# SchaltmichAus.net
KiCad netlist of a schematic drawn in Altium Designer
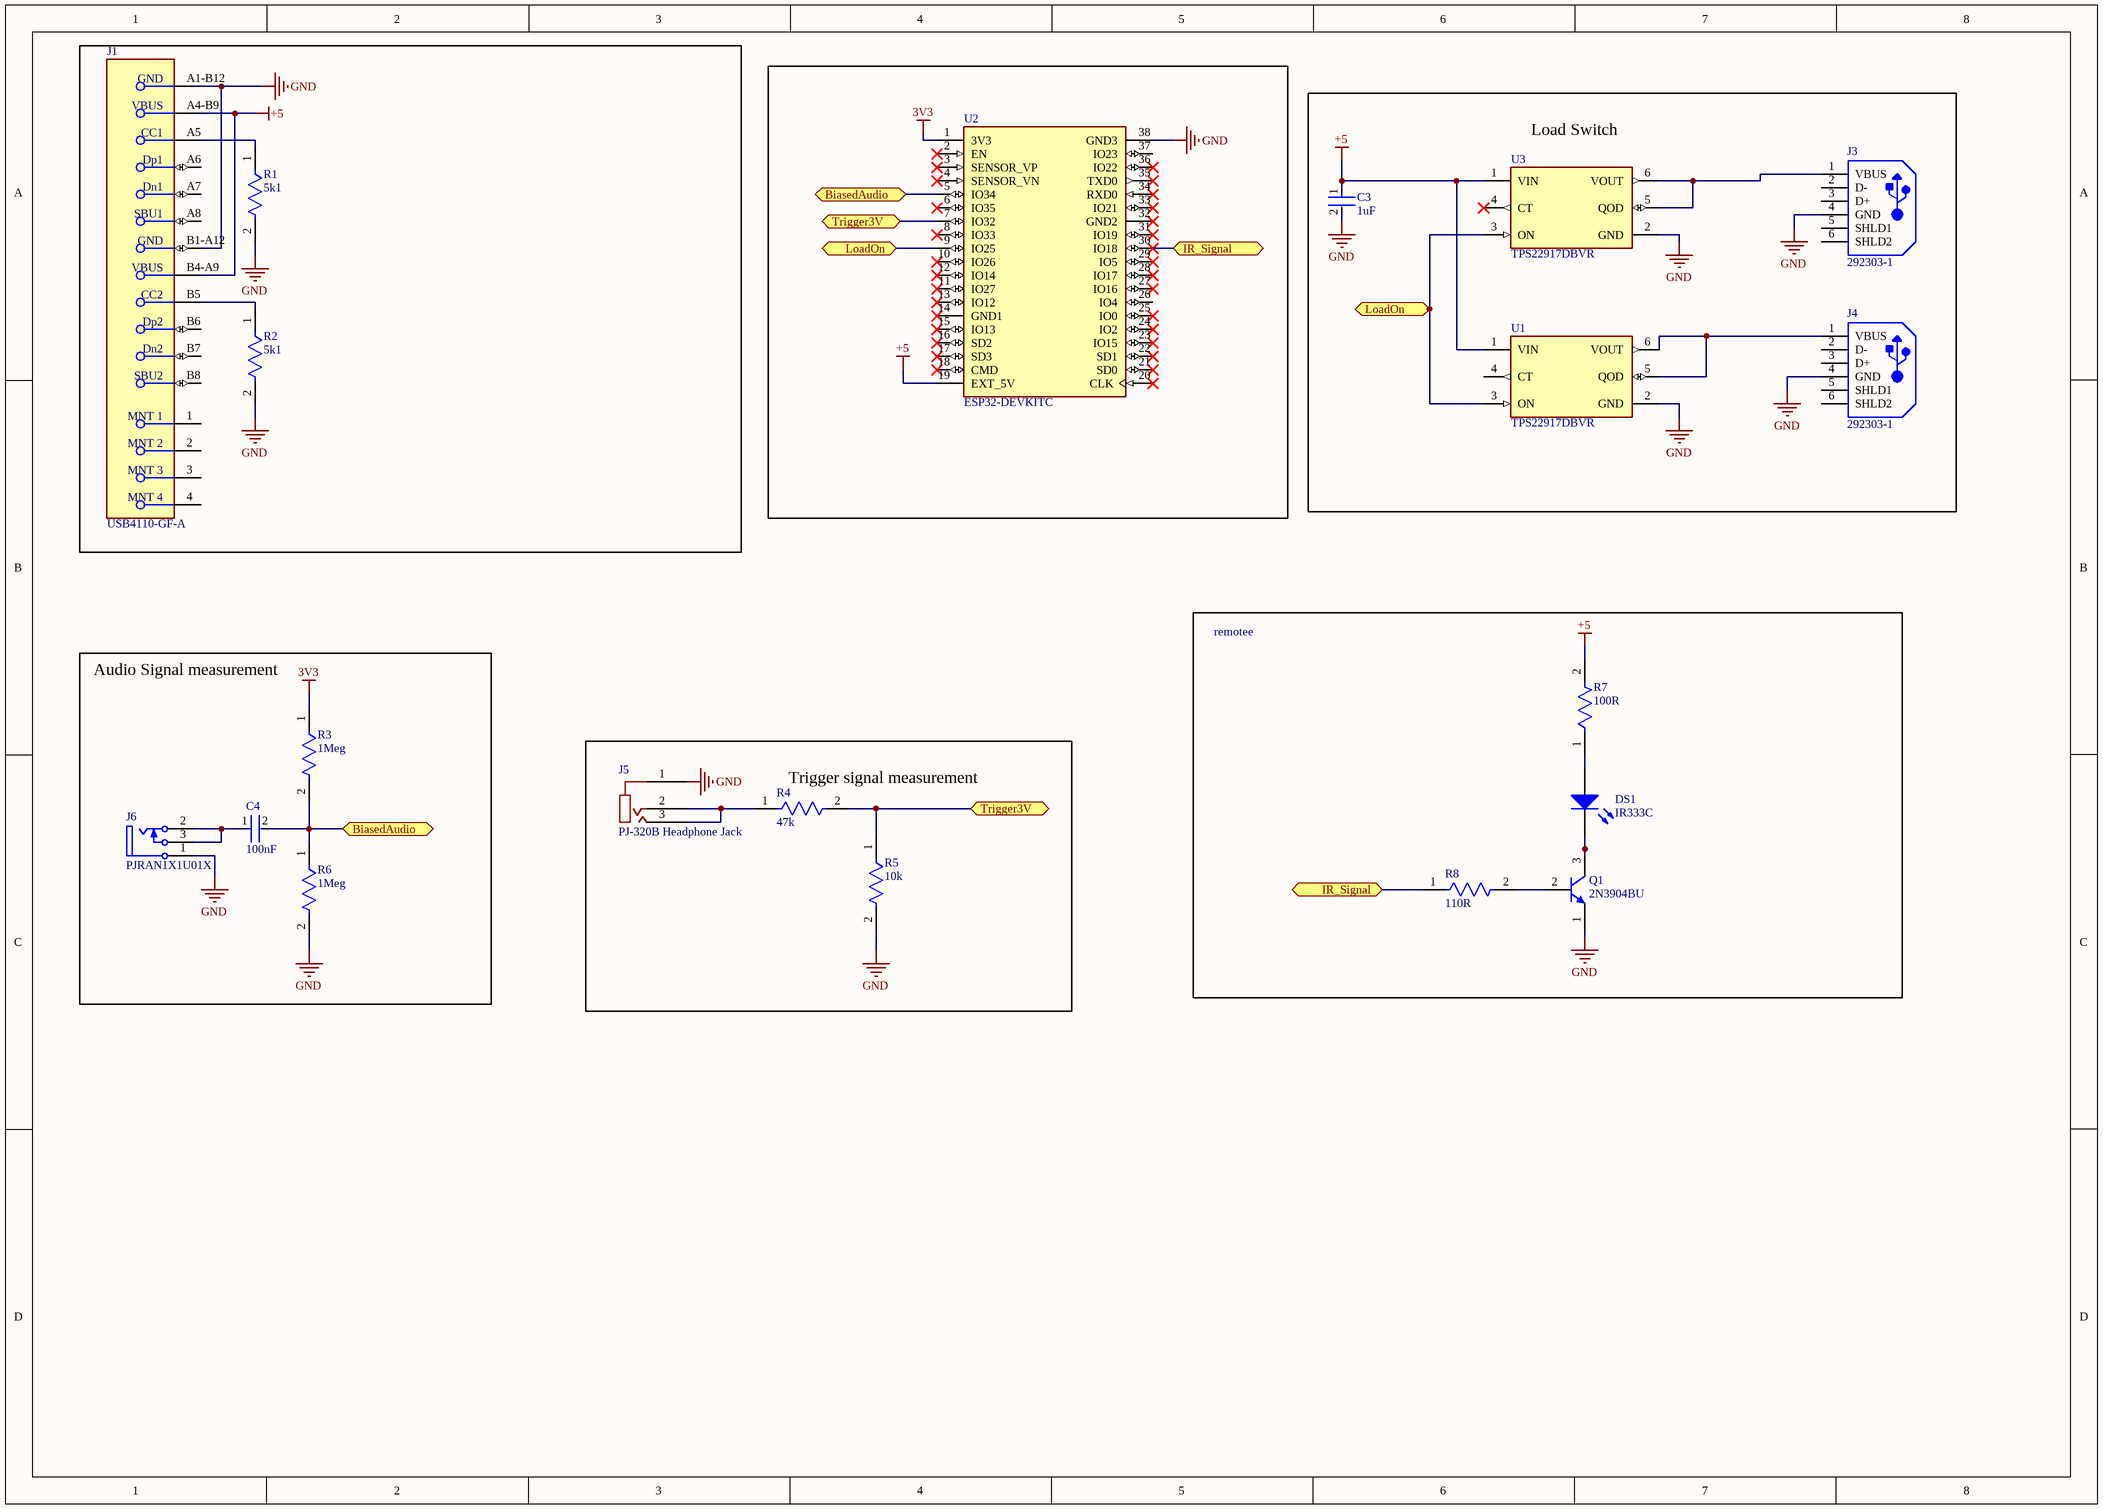
[diagram p0: SchaltmichAus.SchDoc]

(export (version "E")
  (design (tool "Eeschema 10.0.6"))
  (components
    (comp (ref "C3")
      (value "1uF")
      (footprint "FP-CC1206-FD-MFG")
      (description "CAP CER 10UF 50V X5R 1206")
      (fields (field (name "TOLERANCE") "10%"))
      (libsource (lib "Altium Content Vault") (part "b4654b650e69147ec39a6b967a45e02"))
    )
    (comp (ref "C4")
      (value "100nF")
      (footprint "FP-CC1206-FD-MFG")
      (description "CAP CER 10UF 50V X5R 1206")
      (fields (field (name "TOLERANCE") "10%"))
      (libsource (lib "Altium Content Vault") (part "b4654b650e69147ec39a6b967a45e02"))
    )
    (comp (ref "DS1")
      (value "IR333C")
      (footprint "EVRL-IR333C")
      (description "Infrared LED, 1.2 V, -40 to 85 degC, 2-Pin Radial, RoHS, Bulk")
      (fields (field (name "MANUFACTURER") "Everlight Electronics"))
      (libsource (lib "Altium Content Vault") (part "LED-AK-2"))
    )
    (comp (ref "J1")
      (value "USB4110-GF-A")
      (footprint "FP-USB4110-GF-A-MFG")
      (description "CONN USB 2.0 TYPE-C R/A SMT")
      (fields
        (field (name "OCTOPART") "https://octopart.com/usb4110-gf-a-gct-103941985")
        (field (name "MANUFACTURER") "GCT")
      )
      (libsource (lib "Altium Content Vault") (part "e23f2b38bb3c3f98e683ebab9ede730"))
    )
    (comp (ref "J3")
      (value "292303-1")
      (footprint "TE-292303-1_V")
      (fields (field (name "MANUFACTURER") "TE Connectivity"))
      (libsource (lib "Altium Content Vault") (part "USB-4-2SHLD"))
    )
    (comp (ref "J4")
      (value "292303-1")
      (footprint "TE-292303-1_V")
      (fields (field (name "MANUFACTURER") "TE Connectivity"))
      (libsource (lib "Altium Content Vault") (part "USB-4-2SHLD"))
    )
    (comp (ref "J5")
      (value "PJ-320B Headphone Jack")
      (footprint "New footprint 1")
      (description "200mA 3.5mm Headphone Jack 30V SMD Audio Connectors ROHS")
      (libsource (lib "Niko Leimegger") (part "PJ-320BSurface Mount Headphone Jack"))
    )
    (comp (ref "J6")
      (value "PJRAN1X1U01X")
      (footprint "SWIT-PJRAN1X1U01X_V")
      (description "Female Phono Jack, 3 Position, Height 13 mm, Tail Length 4 mm, RoHS, Bulk")
      (fields (field (name "TOLERANCE") "10%"))
      (libsource (lib "Altium Content Vault") (part "JACK-2CD3-TN"))
    )
    (comp (ref "Q1")
      (value "2N3904BU")
      (footprint "FAIR-TO-92")
      (description "NPN General-Purpose Amplifier, 40 V VCEO, 0.2 A, -55 to 150 degC, 2-Pin TO-92, RoHS, Bulk")
      (fields (field (name "MANUFACTURER") "FairchildSemiconductor"))
      (libsource (lib "Altium Content Vault") (part "NPN-E1B2C3-3"))
    )
    (comp (ref "R1")
      (value "5k1")
      (footprint "FP-CRGP1206-IPC_C")
      (description "CRGP1206 100KΩ 0.5W ±100ppm/°C 1% 200V")
      (fields (field (name "MANUFACTURER") "TE") (field (name "TOLERANCE") "0.01"))
      (libsource (lib "Altium Content Vault") (part "1029c3af85768c4190bb7ad29bc67b5"))
    )
    (comp (ref "R2")
      (value "5k1")
      (footprint "FP-CRGP1206-IPC_C")
      (description "CRGP1206 100KΩ 0.5W ±100ppm/°C 1% 200V")
      (fields (field (name "MANUFACTURER") "TE") (field (name "TOLERANCE") "0.01"))
      (libsource (lib "Altium Content Vault") (part "1029c3af85768c4190bb7ad29bc67b5"))
    )
    (comp (ref "R3")
      (value "1Meg")
      (footprint "FP-CRGP1206-IPC_C")
      (description "CRGP1206 100KΩ 0.5W ±100ppm/°C 1% 200V")
      (fields (field (name "MANUFACTURER") "TE") (field (name "TOLERANCE") "0.01"))
      (libsource (lib "Altium Content Vault") (part "1029c3af85768c4190bb7ad29bc67b5"))
    )
    (comp (ref "R4")
      (value "47k")
      (footprint "FP-CRGP1206-IPC_C")
      (description "CRGP1206 100KΩ 0.5W ±100ppm/°C 1% 200V")
      (fields (field (name "MANUFACTURER") "TE") (field (name "TOLERANCE") "0.01"))
      (libsource (lib "Altium Content Vault") (part "1029c3af85768c4190bb7ad29bc67b5"))
    )
    (comp (ref "R5")
      (value "10k")
      (footprint "FP-CRGP1206-IPC_C")
      (description "CRGP1206 100KΩ 0.5W ±100ppm/°C 1% 200V")
      (fields (field (name "MANUFACTURER") "TE") (field (name "TOLERANCE") "0.01"))
      (libsource (lib "Altium Content Vault") (part "1029c3af85768c4190bb7ad29bc67b5"))
    )
    (comp (ref "R6")
      (value "1Meg")
      (footprint "FP-CRGP1206-IPC_C")
      (description "CRGP1206 100KΩ 0.5W ±100ppm/°C 1% 200V")
      (fields (field (name "MANUFACTURER") "TE") (field (name "TOLERANCE") "0.01"))
      (libsource (lib "Altium Content Vault") (part "1029c3af85768c4190bb7ad29bc67b5"))
    )
    (comp (ref "R7")
      (value "100R")
      (footprint "FP-CRGP1206-IPC_C")
      (description "CRGP1206 100KΩ 0.5W ±100ppm/°C 1% 200V")
      (fields (field (name "MANUFACTURER") "TE") (field (name "TOLERANCE") "0.01"))
      (libsource (lib "Altium Content Vault") (part "1029c3af85768c4190bb7ad29bc67b5"))
    )
    (comp (ref "R8")
      (value "110R")
      (footprint "FP-CRGP1206-IPC_C")
      (description "CRGP1206 100KΩ 0.5W ±100ppm/°C 1% 200V")
      (fields (field (name "MANUFACTURER") "TE") (field (name "TOLERANCE") "0.01"))
      (libsource (lib "Altium Content Vault") (part "1029c3af85768c4190bb7ad29bc67b5"))
    )
    (comp (ref "U1")
      (value "TPS22917DBVR")
      (footprint "FP-DBV0006A-IPC_A")
      (description "IC PWR SWITCH P-CHAN 1:1 SOT23-6")
      (libsource (lib "Altium Content Vault") (part "79ac4b3a8af48598f911740ea3eee0a"))
    )
    (comp (ref "U2")
      (value "ESP32-DEVKITC")
      (footprint "MODULE_ESP32-DEVKITC")
      (fields (field (name "MF") "Espressif Systems"))
      (libsource (lib "Niko Leimegger") (part "ESP32-DEVKITC"))
    )
    (comp (ref "U3")
      (value "TPS22917DBVR")
      (footprint "FP-DBV0006A-IPC_A")
      (description "IC PWR SWITCH P-CHAN 1:1 SOT23-6")
      (libsource (lib "Altium Content Vault") (part "79ac4b3a8af48598f911740ea3eee0a"))
    )
  )
  (nets
    (net (code "1") (name "+5") (class "Default")
      (node (ref "C3") (pin "1") (pinfunction "1_1") (pintype "passive"))
      (node (ref "J1") (pin "A4-B9") (pinfunction "VBUS_A4-B9") (pintype "power_in"))
      (node (ref "J1") (pin "B4-A9") (pinfunction "VBUS_B4-A9") (pintype "power_in"))
      (node (ref "R7") (pin "2") (pinfunction "2_2") (pintype "passive"))
      (node (ref "U1") (pin "1") (pinfunction "VIN_1") (pintype "power_in"))
      (node (ref "U2") (pin "19") (pinfunction "EXT_5V_19") (pintype "power_in"))
      (node (ref "U3") (pin "1") (pinfunction "VIN_1") (pintype "power_in"))
    )
    (net (code "2") (name "/BiasedAudio") (class "Default")
      (node (ref "C4") (pin "2") (pinfunction "2_2") (pintype "passive"))
      (node (ref "R3") (pin "2") (pinfunction "2_2") (pintype "passive"))
      (node (ref "R6") (pin "1") (pinfunction "1_1") (pintype "passive"))
      (node (ref "U2") (pin "5") (pinfunction "IO34_5") (pintype "bidirectional"))
    )
    (net (code "3") (name "/IR_Signal") (class "Default")
      (node (ref "R8") (pin "1") (pinfunction "1_1") (pintype "passive"))
      (node (ref "U2") (pin "30") (pinfunction "IO18_30") (pintype "bidirectional"))
    )
    (net (code "4") (name "/LoadOn") (class "Default")
      (node (ref "U1") (pin "3") (pinfunction "ON_3") (pintype "input"))
      (node (ref "U2") (pin "9") (pinfunction "IO25_9") (pintype "bidirectional"))
      (node (ref "U3") (pin "3") (pinfunction "ON_3") (pintype "input"))
    )
    (net (code "5") (name "/Trigger3V") (class "Default")
      (node (ref "R4") (pin "2") (pinfunction "2_2") (pintype "passive"))
      (node (ref "R5") (pin "1") (pinfunction "1_1") (pintype "passive"))
      (node (ref "U2") (pin "7") (pinfunction "IO32_7") (pintype "bidirectional"))
    )
    (net (code "6") (name "3V3") (class "Default")
      (node (ref "R3") (pin "1") (pinfunction "1_1") (pintype "passive"))
      (node (ref "U2") (pin "1") (pinfunction "3V3_1") (pintype "power_in"))
    )
    (net (code "7") (name "GND") (class "Default")
      (node (ref "C3") (pin "2") (pinfunction "2_2") (pintype "passive"))
      (node (ref "J1") (pin "A1-B12") (pinfunction "GND_A1-B12") (pintype "passive"))
      (node (ref "J1") (pin "B1-A12") (pinfunction "GND_B1-A12") (pintype "bidirectional"))
      (node (ref "J3") (pin "4") (pinfunction "GND_4") (pintype "passive"))
      (node (ref "J4") (pin "4") (pinfunction "GND_4") (pintype "passive"))
      (node (ref "J5") (pin "1") (pinfunction "1_1") (pintype "passive"))
      (node (ref "J6") (pin "1") (pinfunction "SLEEVE_1") (pintype "passive"))
      (node (ref "Q1") (pin "1") (pinfunction "E_1") (pintype "passive"))
      (node (ref "R1") (pin "2") (pinfunction "2_2") (pintype "passive"))
      (node (ref "R2") (pin "2") (pinfunction "2_2") (pintype "passive"))
      (node (ref "R5") (pin "2") (pinfunction "2_2") (pintype "passive"))
      (node (ref "R6") (pin "2") (pinfunction "2_2") (pintype "passive"))
      (node (ref "U1") (pin "2") (pinfunction "GND_2") (pintype "power_in"))
      (node (ref "U2") (pin "38") (pinfunction "GND3_38") (pintype "power_in"))
      (node (ref "U3") (pin "2") (pinfunction "GND_2") (pintype "power_in"))
    )
    (net (code "8") (name "Net-(DS1-A)") (class "Default")
      (node (ref "DS1") (pin "1") (pinfunction "A_1") (pintype "passive"))
      (node (ref "R7") (pin "1") (pinfunction "1_1") (pintype "passive"))
    )
    (net (code "9") (name "Net-(DS1-K)") (class "Default")
      (node (ref "DS1") (pin "2") (pinfunction "K_2") (pintype "passive"))
      (node (ref "Q1") (pin "3") (pinfunction "C_3") (pintype "passive"))
    )
    (net (code "10") (name "Net-(J1-CC1)") (class "Default")
      (node (ref "J1") (pin "A5") (pinfunction "CC1_A5") (pintype "power_in"))
      (node (ref "R1") (pin "1") (pinfunction "1_1") (pintype "passive"))
    )
    (net (code "11") (name "Net-(J1-CC2)") (class "Default")
      (node (ref "J1") (pin "B5") (pinfunction "CC2_B5") (pintype "power_in"))
      (node (ref "R2") (pin "1") (pinfunction "1_1") (pintype "passive"))
    )
    (net (code "12") (name "Net-(J3-VBUS)") (class "Default")
      (node (ref "J3") (pin "1") (pinfunction "VBUS_1") (pintype "passive"))
      (node (ref "U3") (pin "5") (pinfunction "QOD_5") (pintype "bidirectional"))
      (node (ref "U3") (pin "6") (pinfunction "VOUT_6") (pintype "output"))
    )
    (net (code "13") (name "Net-(J4-VBUS)") (class "Default")
      (node (ref "J4") (pin "1") (pinfunction "VBUS_1") (pintype "passive"))
      (node (ref "U1") (pin "5") (pinfunction "QOD_5") (pintype "bidirectional"))
      (node (ref "U1") (pin "6") (pinfunction "VOUT_6") (pintype "output"))
    )
    (net (code "14") (name "Net-(J5-Pad2)") (class "Default")
      (node (ref "J5") (pin "2") (pinfunction "2_2") (pintype "passive"))
      (node (ref "J5") (pin "3") (pinfunction "3_3") (pintype "passive"))
      (node (ref "R4") (pin "1") (pinfunction "1_1") (pintype "passive"))
    )
    (net (code "15") (name "Net-(J6-SHUNT)") (class "Default")
      (node (ref "C4") (pin "1") (pinfunction "1_1") (pintype "passive"))
      (node (ref "J6") (pin "2") (pinfunction "TIP_2") (pintype "passive"))
      (node (ref "J6") (pin "3") (pinfunction "SHUNT_3") (pintype "passive"))
    )
    (net (code "16") (name "Net-(Q1-B)") (class "Default")
      (node (ref "Q1") (pin "2") (pinfunction "B_2") (pintype "passive"))
      (node (ref "R8") (pin "2") (pinfunction "2_2") (pintype "passive"))
    )
    (net (code "17") (name "unconnected-(J1-Dn1-PadA7)") (class "Default")
      (node (ref "J1") (pin "A7") (pinfunction "Dn1_A7") (pintype "bidirectional"))
    )
    (net (code "18") (name "unconnected-(J1-Dn2-PadB7)") (class "Default")
      (node (ref "J1") (pin "B7") (pinfunction "Dn2_B7") (pintype "bidirectional"))
    )
    (net (code "19") (name "unconnected-(J1-Dp1-PadA6)") (class "Default")
      (node (ref "J1") (pin "A6") (pinfunction "Dp1_A6") (pintype "bidirectional"))
    )
    (net (code "20") (name "unconnected-(J1-Dp2-PadB6)") (class "Default")
      (node (ref "J1") (pin "B6") (pinfunction "Dp2_B6") (pintype "bidirectional"))
    )
    (net (code "21") (name "unconnected-(J1-MNT_1-Pad1)") (class "Default")
      (node (ref "J1") (pin "1") (pinfunction "MNT_1_1") (pintype "passive"))
    )
    (net (code "22") (name "unconnected-(J1-MNT_2-Pad2)") (class "Default")
      (node (ref "J1") (pin "2") (pinfunction "MNT_2_2") (pintype "passive"))
    )
    (net (code "23") (name "unconnected-(J1-MNT_3-Pad3)") (class "Default")
      (node (ref "J1") (pin "3") (pinfunction "MNT_3_3") (pintype "passive"))
    )
    (net (code "24") (name "unconnected-(J1-MNT_4-Pad4)") (class "Default")
      (node (ref "J1") (pin "4") (pinfunction "MNT_4_4") (pintype "passive"))
    )
    (net (code "25") (name "unconnected-(J1-SBU1-PadA8)") (class "Default")
      (node (ref "J1") (pin "A8") (pinfunction "SBU1_A8") (pintype "bidirectional"))
    )
    (net (code "26") (name "unconnected-(J1-SBU2-PadB8)") (class "Default")
      (node (ref "J1") (pin "B8") (pinfunction "SBU2_B8") (pintype "bidirectional"))
    )
    (net (code "27") (name "unconnected-(J3-D+-Pad3)") (class "Default")
      (node (ref "J3") (pin "3") (pinfunction "D+_3") (pintype "passive"))
    )
    (net (code "28") (name "unconnected-(J3-D--Pad2)") (class "Default")
      (node (ref "J3") (pin "2") (pinfunction "D-_2") (pintype "passive"))
    )
    (net (code "29") (name "unconnected-(J3-SHLD1-Pad5)") (class "Default")
      (node (ref "J3") (pin "5") (pinfunction "SHLD1_5") (pintype "passive"))
    )
    (net (code "30") (name "unconnected-(J3-SHLD2-Pad6)") (class "Default")
      (node (ref "J3") (pin "6") (pinfunction "SHLD2_6") (pintype "passive"))
    )
    (net (code "31") (name "unconnected-(J4-D+-Pad3)") (class "Default")
      (node (ref "J4") (pin "3") (pinfunction "D+_3") (pintype "passive"))
    )
    (net (code "32") (name "unconnected-(J4-D--Pad2)") (class "Default")
      (node (ref "J4") (pin "2") (pinfunction "D-_2") (pintype "passive"))
    )
    (net (code "33") (name "unconnected-(J4-SHLD1-Pad5)") (class "Default")
      (node (ref "J4") (pin "5") (pinfunction "SHLD1_5") (pintype "passive"))
    )
    (net (code "34") (name "unconnected-(J4-SHLD2-Pad6)") (class "Default")
      (node (ref "J4") (pin "6") (pinfunction "SHLD2_6") (pintype "passive"))
    )
    (net (code "35") (name "unconnected-(U1-CT-Pad4)") (class "Default")
      (node (ref "U1") (pin "4") (pinfunction "CT_4") (pintype "output"))
    )
    (net (code "36") (name "unconnected-(U2-CLK-Pad20)") (class "Default")
      (node (ref "U2") (pin "20") (pinfunction "CLK_20") (pintype "input+no_connect"))
    )
    (net (code "37") (name "unconnected-(U2-CMD-Pad18)") (class "Default")
      (node (ref "U2") (pin "18") (pinfunction "CMD_18") (pintype "bidirectional+no_connect"))
    )
    (net (code "38") (name "unconnected-(U2-EN-Pad2)") (class "Default")
      (node (ref "U2") (pin "2") (pinfunction "EN_2") (pintype "input+no_connect"))
    )
    (net (code "39") (name "unconnected-(U2-GND1-Pad14)") (class "Default")
      (node (ref "U2") (pin "14") (pinfunction "GND1_14") (pintype "power_in+no_connect"))
    )
    (net (code "40") (name "unconnected-(U2-GND2-Pad32)") (class "Default")
      (node (ref "U2") (pin "32") (pinfunction "GND2_32") (pintype "power_in+no_connect"))
    )
    (net (code "41") (name "unconnected-(U2-IO0-Pad25)") (class "Default")
      (node (ref "U2") (pin "25") (pinfunction "IO0_25") (pintype "bidirectional+no_connect"))
    )
    (net (code "42") (name "unconnected-(U2-IO2-Pad24)") (class "Default")
      (node (ref "U2") (pin "24") (pinfunction "IO2_24") (pintype "bidirectional+no_connect"))
    )
    (net (code "43") (name "unconnected-(U2-IO4-Pad26)") (class "Default")
      (node (ref "U2") (pin "26") (pinfunction "IO4_26") (pintype "bidirectional"))
    )
    (net (code "44") (name "unconnected-(U2-IO5-Pad29)") (class "Default")
      (node (ref "U2") (pin "29") (pinfunction "IO5_29") (pintype "bidirectional+no_connect"))
    )
    (net (code "45") (name "unconnected-(U2-IO12-Pad13)") (class "Default")
      (node (ref "U2") (pin "13") (pinfunction "IO12_13") (pintype "bidirectional+no_connect"))
    )
    (net (code "46") (name "unconnected-(U2-IO13-Pad15)") (class "Default")
      (node (ref "U2") (pin "15") (pinfunction "IO13_15") (pintype "bidirectional+no_connect"))
    )
    (net (code "47") (name "unconnected-(U2-IO14-Pad12)") (class "Default")
      (node (ref "U2") (pin "12") (pinfunction "IO14_12") (pintype "bidirectional+no_connect"))
    )
    (net (code "48") (name "unconnected-(U2-IO15-Pad23)") (class "Default")
      (node (ref "U2") (pin "23") (pinfunction "IO15_23") (pintype "bidirectional+no_connect"))
    )
    (net (code "49") (name "unconnected-(U2-IO16-Pad27)") (class "Default")
      (node (ref "U2") (pin "27") (pinfunction "IO16_27") (pintype "bidirectional+no_connect"))
    )
    (net (code "50") (name "unconnected-(U2-IO17-Pad28)") (class "Default")
      (node (ref "U2") (pin "28") (pinfunction "IO17_28") (pintype "bidirectional+no_connect"))
    )
    (net (code "51") (name "unconnected-(U2-IO19-Pad31)") (class "Default")
      (node (ref "U2") (pin "31") (pinfunction "IO19_31") (pintype "bidirectional+no_connect"))
    )
    (net (code "52") (name "unconnected-(U2-IO21-Pad33)") (class "Default")
      (node (ref "U2") (pin "33") (pinfunction "IO21_33") (pintype "bidirectional+no_connect"))
    )
    (net (code "53") (name "unconnected-(U2-IO22-Pad36)") (class "Default")
      (node (ref "U2") (pin "36") (pinfunction "IO22_36") (pintype "bidirectional+no_connect"))
    )
    (net (code "54") (name "unconnected-(U2-IO23-Pad37)") (class "Default")
      (node (ref "U2") (pin "37") (pinfunction "IO23_37") (pintype "bidirectional"))
    )
    (net (code "55") (name "unconnected-(U2-IO26-Pad10)") (class "Default")
      (node (ref "U2") (pin "10") (pinfunction "IO26_10") (pintype "bidirectional+no_connect"))
    )
    (net (code "56") (name "unconnected-(U2-IO27-Pad11)") (class "Default")
      (node (ref "U2") (pin "11") (pinfunction "IO27_11") (pintype "bidirectional+no_connect"))
    )
    (net (code "57") (name "unconnected-(U2-IO33-Pad8)") (class "Default")
      (node (ref "U2") (pin "8") (pinfunction "IO33_8") (pintype "bidirectional+no_connect"))
    )
    (net (code "58") (name "unconnected-(U2-IO35-Pad6)") (class "Default")
      (node (ref "U2") (pin "6") (pinfunction "IO35_6") (pintype "bidirectional+no_connect"))
    )
    (net (code "59") (name "unconnected-(U2-RXD0-Pad34)") (class "Default")
      (node (ref "U2") (pin "34") (pinfunction "RXD0_34") (pintype "input+no_connect"))
    )
    (net (code "60") (name "unconnected-(U2-SD0-Pad21)") (class "Default")
      (node (ref "U2") (pin "21") (pinfunction "SD0_21") (pintype "bidirectional+no_connect"))
    )
    (net (code "61") (name "unconnected-(U2-SD1-Pad22)") (class "Default")
      (node (ref "U2") (pin "22") (pinfunction "SD1_22") (pintype "bidirectional+no_connect"))
    )
    (net (code "62") (name "unconnected-(U2-SD2-Pad16)") (class "Default")
      (node (ref "U2") (pin "16") (pinfunction "SD2_16") (pintype "bidirectional+no_connect"))
    )
    (net (code "63") (name "unconnected-(U2-SD3-Pad17)") (class "Default")
      (node (ref "U2") (pin "17") (pinfunction "SD3_17") (pintype "bidirectional+no_connect"))
    )
    (net (code "64") (name "unconnected-(U2-SENSOR_VN-Pad4)") (class "Default")
      (node (ref "U2") (pin "4") (pinfunction "SENSOR_VN_4") (pintype "input+no_connect"))
    )
    (net (code "65") (name "unconnected-(U2-SENSOR_VP-Pad3)") (class "Default")
      (node (ref "U2") (pin "3") (pinfunction "SENSOR_VP_3") (pintype "input+no_connect"))
    )
    (net (code "66") (name "unconnected-(U2-TXD0-Pad35)") (class "Default")
      (node (ref "U2") (pin "35") (pinfunction "TXD0_35") (pintype "output+no_connect"))
    )
    (net (code "67") (name "unconnected-(U3-CT-Pad4)") (class "Default")
      (node (ref "U3") (pin "4") (pinfunction "CT_4") (pintype "output+no_connect"))
    )
  )
)
